# CZ101_V1_0.net
KiCad netlist of a schematic drawn in Altium Designer
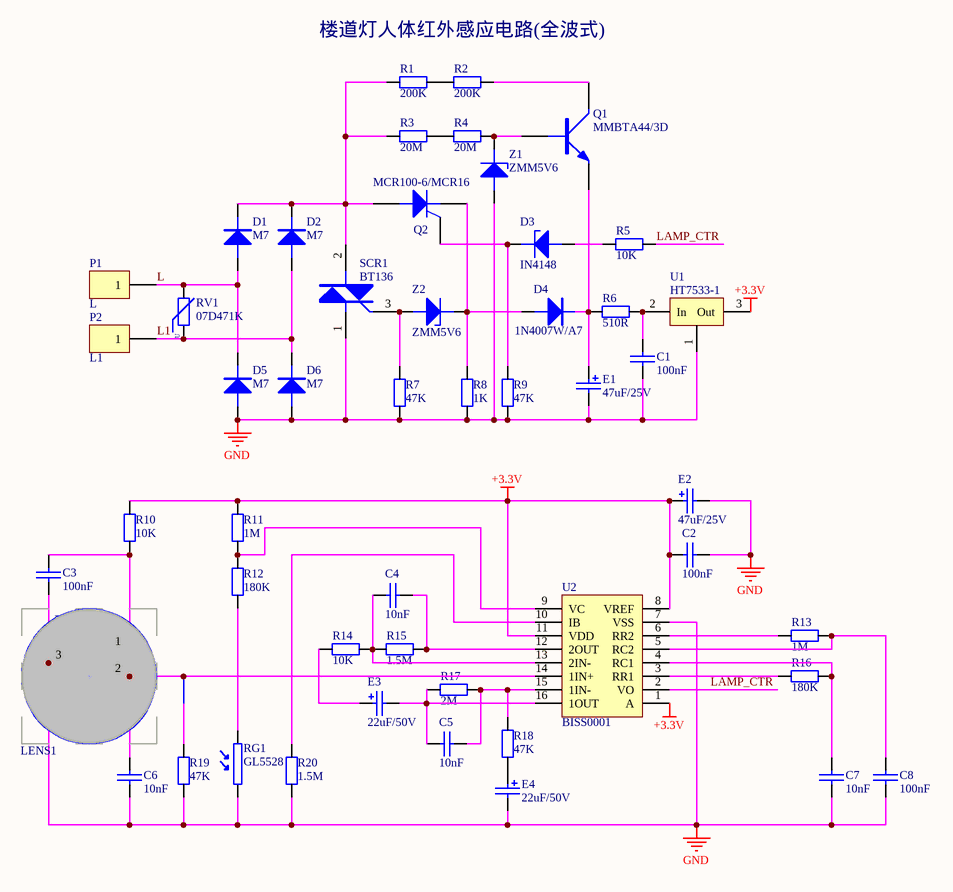
[diagram p0: CZ101_V1.0.SchDoc]

(export (version "E")
  (design (tool "Eeschema 10.0.6"))
  (components
    (comp (ref "C1")
      (value "100nF")
      (footprint "Cheng_Resistor_Capacitor:0805_C1")
      (libsource (lib "Cheng_Resistor_Capacitor") (part "Cap1"))
    )
    (comp (ref "C2")
      (value "100nF")
      (footprint "Cheng_Resistor_Capacitor:0805_C1")
      (libsource (lib "Cheng_Resistor_Capacitor") (part "Cap1"))
    )
    (comp (ref "C3")
      (value "100nF")
      (footprint "Cheng_Resistor_Capacitor:0805_C1")
      (libsource (lib "Cheng_Resistor_Capacitor") (part "Cap1"))
    )
    (comp (ref "C4")
      (value "10nF")
      (footprint "Cheng_Resistor_Capacitor:0805_C1")
      (libsource (lib "Cheng_Resistor_Capacitor") (part "Cap1"))
    )
    (comp (ref "C5")
      (value "10nF")
      (footprint "Cheng_Resistor_Capacitor:0805_C1")
      (libsource (lib "Cheng_Resistor_Capacitor") (part "Cap1"))
    )
    (comp (ref "C6")
      (value "10nF")
      (footprint "Cheng_Resistor_Capacitor:0805_C1")
      (libsource (lib "Cheng_Resistor_Capacitor") (part "Cap1"))
    )
    (comp (ref "C7")
      (value "10nF")
      (footprint "Cheng_Resistor_Capacitor:0805_C1")
      (libsource (lib "Cheng_Resistor_Capacitor") (part "Cap1"))
    )
    (comp (ref "C8")
      (value "100nF")
      (footprint "Cheng_Resistor_Capacitor:0805_C1")
      (libsource (lib "Cheng_Resistor_Capacitor") (part "Cap1"))
    )
    (comp (ref "D1")
      (value "M7")
      (footprint "Cheng_Diode_Transistor:DO-214AC(SMA)")
      (description "SS14,SS24,SS34,M7")
      (libsource (lib "Cheng_Diode_Transistor") (part "Diode-A"))
    )
    (comp (ref "D2")
      (value "M7")
      (footprint "Cheng_Diode_Transistor:DO-214AC(SMA)")
      (description "SS14,SS24,SS34,M7")
      (libsource (lib "Cheng_Diode_Transistor") (part "Diode-A"))
    )
    (comp (ref "D3")
      (value "IN4148")
      (footprint "Cheng_Diode_Transistor:LL-34")
      (libsource (lib "Cheng_Diode_Transistor") (part "Diode-B"))
    )
    (comp (ref "D4")
      (value "1N4007W/A7")
      (footprint "Cheng_Diode_Transistor:SOD-123")
      (description "SS14,SS24,SS34,M7")
      (libsource (lib "Cheng_Diode_Transistor") (part "Diode-A"))
    )
    (comp (ref "D5")
      (value "M7")
      (footprint "Cheng_Diode_Transistor:DO-214AC(SMA)")
      (description "SS14,SS24,SS34,M7")
      (libsource (lib "Cheng_Diode_Transistor") (part "Diode-A"))
    )
    (comp (ref "D6")
      (value "M7")
      (footprint "Cheng_Diode_Transistor:DO-214AC(SMA)")
      (description "SS14,SS24,SS34,M7")
      (libsource (lib "Cheng_Diode_Transistor") (part "Diode-A"))
    )
    (comp (ref "E1")
      (value "47uF/25V")
      (footprint "Cheng_Resistor_Capacitor:CS_47uF/25V")
      (libsource (lib "Cheng_Resistor_Capacitor") (part "Cap Pol1"))
    )
    (comp (ref "E2")
      (value "47uF/25V")
      (footprint "Cheng_Resistor_Capacitor:CS_47uF/25V")
      (libsource (lib "Cheng_Resistor_Capacitor") (part "Cap Pol1"))
    )
    (comp (ref "E3")
      (value "22uF/50V")
      (footprint "Cheng_Resistor_Capacitor:CS_47uF/25V")
      (libsource (lib "Cheng_Resistor_Capacitor") (part "Cap Pol1"))
    )
    (comp (ref "E4")
      (value "22uF/50V")
      (footprint "Cheng_Resistor_Capacitor:CS_47uF/25V")
      (libsource (lib "Cheng_Resistor_Capacitor") (part "Cap Pol1"))
    )
    (comp (ref "LENS1")
      (value "Fresnel lens")
      (footprint "Cheng_Misc Component:Fresnel lens")
      (libsource (lib "Cheng_Misc Component") (part "Fresnel lens"))
    )
    (comp (ref "P1")
      (value "L")
      (footprint "Cheng_Interface Unit:CP3M*8.8")
      (description "Header, 1-Pin")
      (fields (field (name "PUBLISHER") "Altium Limited"))
      (libsource (lib "Cheng_Interface Unit") (part "Header 1"))
    )
    (comp (ref "P2")
      (value "L1")
      (footprint "Cheng_Interface Unit:CP3M*8.8")
      (description "Header, 1-Pin")
      (fields (field (name "PUBLISHER") "Altium Limited"))
      (libsource (lib "Cheng_Interface Unit") (part "Header 1"))
    )
    (comp (ref "PRI1")
      (value "D203S")
      (footprint "D203S")
      (description "D203S, KP500BP")
      (libsource (lib "Cheng_IC") (part "D203S"))
    )
    (comp (ref "Q1")
      (value "MMBTA44/3D")
      (footprint "Cheng_Diode_Transistor:SOT-23")
      (libsource (lib "Cheng_Diode_Transistor") (part "8050"))
    )
    (comp (ref "Q2")
      (value "MCR100-6/MCR16")
      (footprint "Cheng_Diode_Transistor:SOT-23")
      (description "Silicon Controlled Rectifier")
      (fields (field (name "PUBLISHER") "Altium Limited"))
      (libsource (lib "Cheng_Diode_Transistor") (part "MCR100-8"))
    )
    (comp (ref "R1")
      (value "200K")
      (footprint "Cheng_Resistor_Capacitor:1206_R")
      (libsource (lib "") (part "Res1_1"))
    )
    (comp (ref "R2")
      (value "200K")
      (footprint "Cheng_Resistor_Capacitor:1206_R")
      (libsource (lib "") (part "Res1_1"))
    )
    (comp (ref "R3")
      (value "20M")
      (footprint "Cheng_Resistor_Capacitor:0805_R")
      (libsource (lib "") (part "Res1_1"))
    )
    (comp (ref "R4")
      (value "20M")
      (footprint "Cheng_Resistor_Capacitor:0805_R")
      (libsource (lib "") (part "Res1_1"))
    )
    (comp (ref "R5")
      (value "10K")
      (footprint "Cheng_Resistor_Capacitor:1206_R")
      (libsource (lib "") (part "Res1_1"))
    )
    (comp (ref "R6")
      (value "510R")
      (footprint "Cheng_Resistor_Capacitor:0805_R")
      (libsource (lib "") (part "Res1_1"))
    )
    (comp (ref "R7")
      (value "47K")
      (footprint "Cheng_Resistor_Capacitor:0805_R")
      (libsource (lib "Cheng_Resistor_Capacitor") (part "Res1"))
    )
    (comp (ref "R8")
      (value "1K")
      (footprint "Cheng_Resistor_Capacitor:0805_R")
      (libsource (lib "Cheng_Resistor_Capacitor") (part "Res1"))
    )
    (comp (ref "R9")
      (value "47K")
      (footprint "Cheng_Resistor_Capacitor:0805_R")
      (libsource (lib "Cheng_Resistor_Capacitor") (part "Res1"))
    )
    (comp (ref "R10")
      (value "10K")
      (footprint "Cheng_Resistor_Capacitor:0805_R")
      (libsource (lib "Cheng_Resistor_Capacitor") (part "Res1"))
    )
    (comp (ref "R11")
      (value "1M")
      (footprint "Cheng_Resistor_Capacitor:0805_R")
      (libsource (lib "Cheng_Resistor_Capacitor") (part "Res1"))
    )
    (comp (ref "R12")
      (value "180K")
      (footprint "Cheng_Resistor_Capacitor:0805_R")
      (libsource (lib "Cheng_Resistor_Capacitor") (part "Res1"))
    )
    (comp (ref "R13")
      (value "1M")
      (footprint "Cheng_Resistor_Capacitor:0805_R")
      (libsource (lib "") (part "Res1_1"))
    )
    (comp (ref "R14")
      (value "10K")
      (footprint "Cheng_Resistor_Capacitor:0805_R")
      (libsource (lib "") (part "Res1_1"))
    )
    (comp (ref "R15")
      (value "1.5M")
      (footprint "Cheng_Resistor_Capacitor:0805_R")
      (libsource (lib "") (part "Res1_1"))
    )
    (comp (ref "R16")
      (value "180K")
      (footprint "Cheng_Resistor_Capacitor:0805_R")
      (libsource (lib "") (part "Res1_2"))
    )
    (comp (ref "R17")
      (value "2M")
      (footprint "Cheng_Resistor_Capacitor:0805_R")
      (libsource (lib "") (part "Res1_1"))
    )
    (comp (ref "R18")
      (value "47K")
      (footprint "Cheng_Resistor_Capacitor:0805_R")
      (libsource (lib "Cheng_Resistor_Capacitor") (part "Res1"))
    )
    (comp (ref "R19")
      (value "47K")
      (footprint "Cheng_Resistor_Capacitor:0805_R")
      (libsource (lib "Cheng_Resistor_Capacitor") (part "Res1"))
    )
    (comp (ref "R20")
      (value "1.5M")
      (footprint "Cheng_Resistor_Capacitor:0805_R")
      (libsource (lib "Cheng_Resistor_Capacitor") (part "Res1"))
    )
    (comp (ref "RG1")
      (value "GL5528")
      (footprint "Cheng_Resistor_Capacitor:R5537")
      (libsource (lib "Cheng_Resistor_Capacitor") (part "GL5539"))
    )
    (comp (ref "RV1")
      (value "07D471K")
      (footprint "Cheng_Resistor_Capacitor:RV-5MM")
      (libsource (lib "Cheng_Resistor_Capacitor") (part "Res Piezo Varistor"))
    )
    (comp (ref "SCR1")
      (value "BT136")
      (footprint "Cheng_Manostat:TO-252")
      (libsource (lib "Cheng_Diode_Transistor") (part "TRIAC"))
    )
    (comp (ref "U1")
      (value "HT7533-1")
      (footprint "SOT-89")
      (description "HT7533; Output 500mA; Iq: 5uA, max= 7uA")
      (libsource (lib "Cheng_Manostat") (part "HT7833"))
    )
    (comp (ref "U2")
      (value "BISS0001")
      (footprint "Cheng_IC:SO-16")
      (description "BISS0001, CSC0001")
      (libsource (lib "Cheng_IC") (part "BISS0001"))
    )
    (comp (ref "Z1")
      (value "ZMM5V6")
      (footprint "Cheng_Diode_Transistor:LL-34")
      (libsource (lib "Cheng_Diode_Transistor") (part "Diode-B"))
    )
    (comp (ref "Z2")
      (value "ZMM5V6")
      (footprint "Cheng_Diode_Transistor:LL-34")
      (libsource (lib "Cheng_Diode_Transistor") (part "Diode-B"))
    )
  )
  (nets
    (net (code "1") (name "+3.3V") (class "Default")
      (node (ref "C2") (pin "1") (pinfunction "1_1") (pintype "passive"))
      (node (ref "E2") (pin "1") (pinfunction "1_1") (pintype "passive"))
      (node (ref "R10") (pin "2") (pinfunction "2_2") (pintype "passive"))
      (node (ref "R11") (pin "2") (pinfunction "2_2") (pintype "passive"))
      (node (ref "U1") (pin "3") (pinfunction "Out_3") (pintype "passive"))
      (node (ref "U2") (pin "1") (pinfunction "A_1") (pintype "passive"))
      (node (ref "U2") (pin "11") (pinfunction "VDD_11") (pintype "passive"))
      (node (ref "U2") (pin "8") (pinfunction "VREF_8") (pintype "passive"))
    )
    (net (code "2") (name "/L") (class "Default")
      (node (ref "D1") (pin "A") (pinfunction "1_A") (pintype "passive"))
      (node (ref "D5") (pin "K") (pinfunction "2_K") (pintype "passive"))
      (node (ref "P1") (pin "1") (pinfunction "1_1") (pintype "passive"))
      (node (ref "RV1") (pin "2") (pinfunction "2_2") (pintype "passive"))
    )
    (net (code "3") (name "/L1") (class "Default")
      (node (ref "D2") (pin "A") (pinfunction "1_A") (pintype "passive"))
      (node (ref "D6") (pin "K") (pinfunction "2_K") (pintype "passive"))
      (node (ref "P2") (pin "1") (pinfunction "1_1") (pintype "passive"))
      (node (ref "RV1") (pin "1") (pinfunction "1_1") (pintype "passive"))
    )
    (net (code "4") (name "/LAMP_CTR") (class "Default")
      (node (ref "R5") (pin "2") (pinfunction "2_2") (pintype "passive"))
      (node (ref "U2") (pin "2") (pinfunction "VO_2") (pintype "passive"))
    )
    (net (code "5") (name "GND") (class "Default")
      (node (ref "C1") (pin "2") (pinfunction "2_2") (pintype "passive"))
      (node (ref "C2") (pin "2") (pinfunction "2_2") (pintype "passive"))
      (node (ref "C3") (pin "2") (pinfunction "2_2") (pintype "passive"))
      (node (ref "C6") (pin "2") (pinfunction "2_2") (pintype "passive"))
      (node (ref "C7") (pin "2") (pinfunction "2_2") (pintype "passive"))
      (node (ref "C8") (pin "1") (pinfunction "1_1") (pintype "passive"))
      (node (ref "D5") (pin "A") (pinfunction "1_A") (pintype "passive"))
      (node (ref "D6") (pin "A") (pinfunction "1_A") (pintype "passive"))
      (node (ref "E1") (pin "2") (pinfunction "2_2") (pintype "passive"))
      (node (ref "E2") (pin "2") (pinfunction "2_2") (pintype "passive"))
      (node (ref "E4") (pin "2") (pinfunction "2_2") (pintype "passive"))
      (node (ref "PRI1") (pin "3") (pinfunction "G_3") (pintype "passive"))
      (node (ref "R19") (pin "1") (pinfunction "1_1") (pintype "passive"))
      (node (ref "R20") (pin "1") (pinfunction "1_1") (pintype "passive"))
      (node (ref "R7") (pin "1") (pinfunction "1_1") (pintype "passive"))
      (node (ref "R8") (pin "1") (pinfunction "1_1") (pintype "passive"))
      (node (ref "R9") (pin "1") (pinfunction "1_1") (pintype "passive"))
      (node (ref "RG1") (pin "1") (pinfunction "1_1") (pintype "passive"))
      (node (ref "SCR1") (pin "1") (pinfunction "T_1") (pintype "passive"))
      (node (ref "U1") (pin "1") (pinfunction "GND_1") (pintype "passive"))
      (node (ref "U2") (pin "7") (pinfunction "VSS_7") (pintype "passive"))
      (node (ref "Z1") (pin "A") (pinfunction "1_A") (pintype "passive"))
    )
    (net (code "6") (name "Net-(D1-2)") (class "Default")
      (node (ref "D1") (pin "K") (pinfunction "2_K") (pintype "passive"))
      (node (ref "D2") (pin "K") (pinfunction "2_K") (pintype "passive"))
      (node (ref "Q2") (pin "3") (pinfunction "A_3") (pintype "passive"))
      (node (ref "R1") (pin "1") (pinfunction "1_1") (pintype "passive"))
      (node (ref "R3") (pin "1") (pinfunction "1_1") (pintype "passive"))
      (node (ref "SCR1") (pin "2") (pinfunction "T_2") (pintype "passive"))
    )
    (net (code "7") (name "Net-(D3-1)") (class "Default")
      (node (ref "D3") (pin "A") (pinfunction "1_A") (pintype "passive"))
      (node (ref "R5") (pin "1") (pinfunction "1_1") (pintype "passive"))
    )
    (net (code "8") (name "Net-(D3-2)") (class "Default")
      (node (ref "D3") (pin "K") (pinfunction "2_K") (pintype "passive"))
      (node (ref "Q2") (pin "2") (pinfunction "G_2") (pintype "passive"))
      (node (ref "R9") (pin "2") (pinfunction "2_2") (pintype "passive"))
    )
    (net (code "9") (name "Net-(D4-1)") (class "Default")
      (node (ref "D4") (pin "A") (pinfunction "1_A") (pintype "passive"))
      (node (ref "Q2") (pin "1") (pinfunction "K_1") (pintype "passive"))
      (node (ref "R8") (pin "2") (pinfunction "2_2") (pintype "passive"))
      (node (ref "Z2") (pin "K") (pinfunction "2_K") (pintype "passive"))
    )
    (net (code "10") (name "Net-(D4-2)") (class "Default")
      (node (ref "D4") (pin "K") (pinfunction "2_K") (pintype "passive"))
      (node (ref "E1") (pin "1") (pinfunction "1_1") (pintype "passive"))
      (node (ref "Q1") (pin "2") (pinfunction "E_2") (pintype "passive"))
      (node (ref "R6") (pin "1") (pinfunction "1_1") (pintype "passive"))
    )
    (net (code "11") (name "Net-(E3-Pad1)") (class "Default")
      (node (ref "E3") (pin "1") (pinfunction "1_1") (pintype "passive"))
      (node (ref "R14") (pin "1") (pinfunction "1_1") (pintype "passive"))
    )
    (net (code "12") (name "Net-(E4-Pad1)") (class "Default")
      (node (ref "E4") (pin "1") (pinfunction "1_1") (pintype "passive"))
      (node (ref "R18") (pin "1") (pinfunction "1_1") (pintype "passive"))
    )
    (net (code "13") (name "Net-(PRI1-D)") (class "Default")
      (node (ref "C3") (pin "1") (pinfunction "1_1") (pintype "passive"))
      (node (ref "PRI1") (pin "1") (pinfunction "D_1") (pintype "passive"))
      (node (ref "R10") (pin "1") (pinfunction "1_1") (pintype "passive"))
    )
    (net (code "14") (name "Net-(PRI1-S)") (class "Default")
      (node (ref "C6") (pin "1") (pinfunction "1_1") (pintype "passive"))
      (node (ref "PRI1") (pin "2") (pinfunction "S_2") (pintype "passive"))
      (node (ref "R19") (pin "2") (pinfunction "2_2") (pintype "passive"))
      (node (ref "U2") (pin "14") (pinfunction "1IN+_14") (pintype "passive"))
    )
    (net (code "15") (name "Net-(Q1-B)") (class "Default")
      (node (ref "Q1") (pin "1") (pinfunction "B_1") (pintype "passive"))
      (node (ref "R4") (pin "2") (pinfunction "2_2") (pintype "passive"))
      (node (ref "Z1") (pin "K") (pinfunction "2_K") (pintype "passive"))
    )
    (net (code "16") (name "Net-(Q1-C)") (class "Default")
      (node (ref "Q1") (pin "3") (pinfunction "C_3") (pintype "passive"))
      (node (ref "R2") (pin "2") (pinfunction "2_2") (pintype "passive"))
    )
    (net (code "17") (name "Net-(R1-Pad2)") (class "Default")
      (node (ref "R1") (pin "2") (pinfunction "2_2") (pintype "passive"))
      (node (ref "R2") (pin "1") (pinfunction "1_1") (pintype "passive"))
    )
    (net (code "18") (name "Net-(R3-Pad2)") (class "Default")
      (node (ref "R3") (pin "2") (pinfunction "2_2") (pintype "passive"))
      (node (ref "R4") (pin "1") (pinfunction "1_1") (pintype "passive"))
    )
    (net (code "19") (name "Net-(R12-Pad1)") (class "Default")
      (node (ref "R12") (pin "1") (pinfunction "1_1") (pintype "passive"))
      (node (ref "RG1") (pin "2") (pinfunction "2_2") (pintype "passive"))
    )
    (net (code "20") (name "Net-(SCR1-G)") (class "Default")
      (node (ref "R7") (pin "2") (pinfunction "2_2") (pintype "passive"))
      (node (ref "SCR1") (pin "3") (pinfunction "G_3") (pintype "passive"))
      (node (ref "Z2") (pin "A") (pinfunction "1_A") (pintype "passive"))
    )
    (net (code "21") (name "Net-(U1-In)") (class "Default")
      (node (ref "C1") (pin "1") (pinfunction "1_1") (pintype "passive"))
      (node (ref "R6") (pin "2") (pinfunction "2_2") (pintype "passive"))
      (node (ref "U1") (pin "2") (pinfunction "In_2") (pintype "passive"))
    )
    (net (code "22") (name "Net-(U2-1IN-)") (class "Default")
      (node (ref "C5") (pin "1") (pinfunction "1_1") (pintype "passive"))
      (node (ref "R17") (pin "2") (pinfunction "2_2") (pintype "passive"))
      (node (ref "R18") (pin "2") (pinfunction "2_2") (pintype "passive"))
      (node (ref "U2") (pin "15") (pinfunction "1IN-_15") (pintype "passive"))
    )
    (net (code "23") (name "Net-(U2-1OUT)") (class "Default")
      (node (ref "C5") (pin "2") (pinfunction "2_2") (pintype "passive"))
      (node (ref "E3") (pin "2") (pinfunction "2_2") (pintype "passive"))
      (node (ref "R17") (pin "1") (pinfunction "1_1") (pintype "passive"))
      (node (ref "U2") (pin "16") (pinfunction "1OUT_16") (pintype "passive"))
    )
    (net (code "24") (name "Net-(U2-2IN-)") (class "Default")
      (node (ref "C4") (pin "1") (pinfunction "1_1") (pintype "passive"))
      (node (ref "R14") (pin "2") (pinfunction "2_2") (pintype "passive"))
      (node (ref "R15") (pin "1") (pinfunction "1_1") (pintype "passive"))
      (node (ref "U2") (pin "13") (pinfunction "2IN-_13") (pintype "passive"))
    )
    (net (code "25") (name "Net-(U2-2OUT)") (class "Default")
      (node (ref "C4") (pin "2") (pinfunction "2_2") (pintype "passive"))
      (node (ref "R15") (pin "2") (pinfunction "2_2") (pintype "passive"))
      (node (ref "U2") (pin "12") (pinfunction "2OUT_12") (pintype "passive"))
    )
    (net (code "26") (name "Net-(U2-IB)") (class "Default")
      (node (ref "R20") (pin "2") (pinfunction "2_2") (pintype "passive"))
      (node (ref "U2") (pin "10") (pinfunction "IB_10") (pintype "passive"))
    )
    (net (code "27") (name "Net-(U2-RC1)") (class "Default")
      (node (ref "C7") (pin "1") (pinfunction "1_1") (pintype "passive"))
      (node (ref "R16") (pin "1") (pinfunction "1_1") (pintype "passive"))
      (node (ref "U2") (pin "4") (pinfunction "RC1_4") (pintype "passive"))
    )
    (net (code "28") (name "Net-(U2-RC2)") (class "Default")
      (node (ref "C8") (pin "2") (pinfunction "2_2") (pintype "passive"))
      (node (ref "R13") (pin "2") (pinfunction "2_2") (pintype "passive"))
      (node (ref "U2") (pin "5") (pinfunction "RC2_5") (pintype "passive"))
    )
    (net (code "29") (name "Net-(U2-RR1)") (class "Default")
      (node (ref "R16") (pin "2") (pinfunction "2_2") (pintype "passive"))
      (node (ref "U2") (pin "3") (pinfunction "RR1_3") (pintype "passive"))
    )
    (net (code "30") (name "Net-(U2-RR2)") (class "Default")
      (node (ref "R13") (pin "1") (pinfunction "1_1") (pintype "passive"))
      (node (ref "U2") (pin "6") (pinfunction "RR2_6") (pintype "passive"))
    )
    (net (code "31") (name "Net-(U2-VC)") (class "Default")
      (node (ref "R11") (pin "1") (pinfunction "1_1") (pintype "passive"))
      (node (ref "R12") (pin "2") (pinfunction "2_2") (pintype "passive"))
      (node (ref "U2") (pin "9") (pinfunction "VC_9") (pintype "passive"))
    )
  )
)
